# ultra-low-noise-psu-NEG-v0001.net
KiCad netlist of a schematic drawn in EAGLE
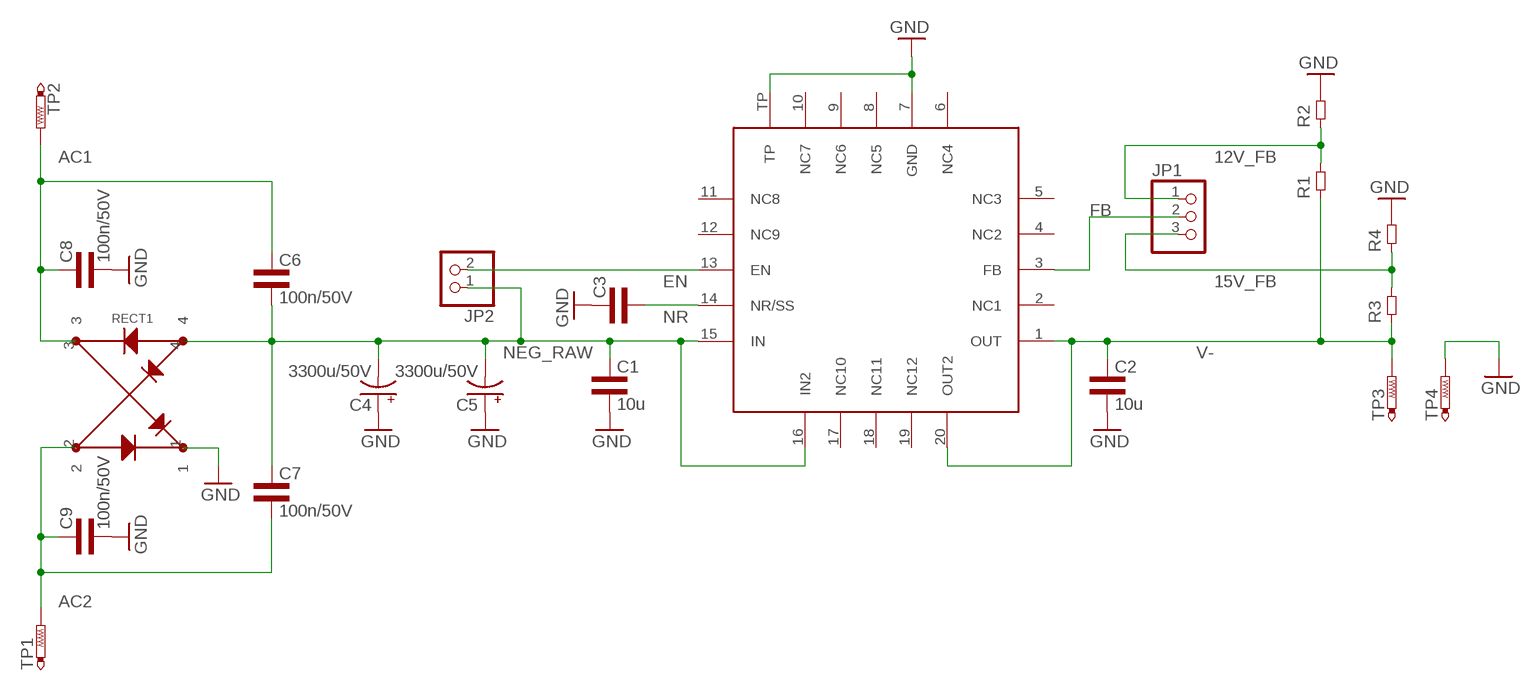
[diagram p0: schematic, sheet 1]

(export (version "E")
  (design (tool "Eeschema 10.0.6"))
  (components
    (comp (ref "C1")
      (value "10u")
      (footprint "eagle-import:0805L3")
      (libsource (lib "eagle-import") (part "CAP0805L3"))
    )
    (comp (ref "C2")
      (value "10u")
      (footprint "eagle-import:0805L3")
      (libsource (lib "eagle-import") (part "CAP0805L3"))
    )
    (comp (ref "C3")
      (value "CAP0603L3")
      (footprint "eagle-import:0603L3")
      (libsource (lib "eagle-import") (part "CAP0603L3"))
    )
    (comp (ref "C4")
      (value "3300u/50V")
      (footprint "eagle-import:E7,5-18")
      (libsource (lib "eagle-import") (part "CPOL-USE7.5-18"))
    )
    (comp (ref "C5")
      (value "3300u/50V")
      (footprint "eagle-import:E7,5-18")
      (libsource (lib "eagle-import") (part "CPOL-USE7.5-18"))
    )
    (comp (ref "C6")
      (value "100n/50V")
      (footprint "eagle-import:0805L3")
      (libsource (lib "eagle-import") (part "CAP0805L3"))
    )
    (comp (ref "C7")
      (value "100n/50V")
      (footprint "eagle-import:0805L3")
      (libsource (lib "eagle-import") (part "CAP0805L3"))
    )
    (comp (ref "C8")
      (value "100n/50V")
      (footprint "eagle-import:0805L3")
      (libsource (lib "eagle-import") (part "CAP0805L3"))
    )
    (comp (ref "C9")
      (value "100n/50V")
      (footprint "eagle-import:0805L3")
      (libsource (lib "eagle-import") (part "CAP0805L3"))
    )
    (comp (ref "JP1")
      (value "PINHD-1X3")
      (footprint "eagle-import:1X03")
      (libsource (lib "eagle-import") (part "PINHD-1X3"))
    )
    (comp (ref "JP2")
      (value "PINHD-1X2")
      (footprint "eagle-import:1X02")
      (libsource (lib "eagle-import") (part "PINHD-1X2"))
    )
    (comp (ref "R1")
      (value "RES0603L3")
      (footprint "eagle-import:0603L3")
      (libsource (lib "eagle-import") (part "RES0603L3"))
    )
    (comp (ref "R2")
      (value "RES0603L3")
      (footprint "eagle-import:0603L3")
      (libsource (lib "eagle-import") (part "RES0603L3"))
    )
    (comp (ref "R3")
      (value "RES0603L3")
      (footprint "eagle-import:0603L3")
      (libsource (lib "eagle-import") (part "RES0603L3"))
    )
    (comp (ref "R4")
      (value "RES0603L3")
      (footprint "eagle-import:0603L3")
      (libsource (lib "eagle-import") (part "RES0603L3"))
    )
    (comp (ref "RECT1")
      (value "RECTIFIER_Z4GP206")
      (footprint "eagle-import:RECTIFIER_ABS-4")
      (libsource (lib "eagle-import") (part "RECTIFIER_Z4GP206"))
    )
    (comp (ref "TP1")
      (value "PTR1PAD1-20")
      (footprint "eagle-import:P1-20")
      (libsource (lib "eagle-import") (part "PTR1PAD1-20"))
    )
    (comp (ref "TP2")
      (value "PTR1PAD1-20")
      (footprint "eagle-import:P1-20")
      (libsource (lib "eagle-import") (part "PTR1PAD1-20"))
    )
    (comp (ref "TP3")
      (value "PTR1PAD1-20")
      (footprint "eagle-import:P1-20")
      (libsource (lib "eagle-import") (part "PTR1PAD1-20"))
    )
    (comp (ref "TP4")
      (value "PTR1PAD1-20")
      (footprint "eagle-import:P1-20")
      (libsource (lib "eagle-import") (part "PTR1PAD1-20"))
    )
    (comp (ref "U$1")
      (value "POWER-SUPPLY_POS_V1_TI_LDO_TPS7A3301RGWT")
      (footprint "eagle-import:POWER-SUPPLY_POS_V1_TI_LDO_VQFN-20")
      (libsource (lib "eagle-import") (part "POWER-SUPPLY_POS_V1_TI_LDO_TPS7A3301RGWT"))
    )
  )
  (nets
    (net (code "1") (name "/12V_FB") (class "Default")
      (node (ref "JP1") (pin "1") (pinfunction "1_1") (pintype "passive"))
      (node (ref "R1") (pin "P$2") (pinfunction "2_P$2") (pintype "bidirectional"))
      (node (ref "R2") (pin "P$1") (pinfunction "1_P$1") (pintype "bidirectional"))
    )
    (net (code "2") (name "/15V_FB") (class "Default")
      (node (ref "JP1") (pin "3") (pinfunction "3_3") (pintype "passive"))
      (node (ref "R3") (pin "P$2") (pinfunction "2_P$2") (pintype "bidirectional"))
      (node (ref "R4") (pin "P$1") (pinfunction "1_P$1") (pintype "bidirectional"))
    )
    (net (code "3") (name "/AC1") (class "Default")
      (node (ref "C6") (pin "1") (pinfunction "1_1") (pintype "bidirectional"))
      (node (ref "C8") (pin "1") (pinfunction "1_1") (pintype "bidirectional"))
      (node (ref "RECT1") (pin "3") (pinfunction "3_3") (pintype "bidirectional"))
      (node (ref "TP2") (pin "TP") (pinfunction "TP_TP") (pintype "input"))
    )
    (net (code "4") (name "/AC2") (class "Default")
      (node (ref "C7") (pin "2") (pinfunction "2_2") (pintype "bidirectional"))
      (node (ref "C9") (pin "1") (pinfunction "1_1") (pintype "bidirectional"))
      (node (ref "RECT1") (pin "2") (pinfunction "2_2") (pintype "bidirectional"))
      (node (ref "TP1") (pin "TP") (pinfunction "TP_TP") (pintype "input"))
    )
    (net (code "5") (name "/EN") (class "Default")
      (node (ref "JP2") (pin "2") (pinfunction "2_2") (pintype "passive"))
      (node (ref "U$1") (pin "13") (pinfunction "EN_13") (pintype "bidirectional"))
    )
    (net (code "6") (name "/FB") (class "Default")
      (node (ref "JP1") (pin "2") (pinfunction "2_2") (pintype "passive"))
      (node (ref "U$1") (pin "3") (pinfunction "FB_3") (pintype "bidirectional"))
    )
    (net (code "7") (name "/NEG_RAW") (class "Default")
      (node (ref "C1") (pin "1") (pinfunction "1_1") (pintype "bidirectional"))
      (node (ref "C4") (pin "-") (pinfunction "-_-") (pintype "passive"))
      (node (ref "C5") (pin "-") (pinfunction "-_-") (pintype "passive"))
      (node (ref "C6") (pin "2") (pinfunction "2_2") (pintype "bidirectional"))
      (node (ref "C7") (pin "1") (pinfunction "1_1") (pintype "bidirectional"))
      (node (ref "JP2") (pin "1") (pinfunction "1_1") (pintype "passive"))
      (node (ref "RECT1") (pin "4") (pinfunction "4_4") (pintype "bidirectional"))
      (node (ref "U$1") (pin "15") (pinfunction "IN_15") (pintype "bidirectional"))
      (node (ref "U$1") (pin "16") (pinfunction "IN2_16") (pintype "bidirectional"))
    )
    (net (code "8") (name "/NR") (class "Default")
      (node (ref "C3") (pin "P$2") (pinfunction "2_P$2") (pintype "bidirectional"))
      (node (ref "U$1") (pin "14") (pinfunction "NR/SS_14") (pintype "bidirectional"))
    )
    (net (code "9") (name "/V-") (class "Default")
      (node (ref "C2") (pin "1") (pinfunction "1_1") (pintype "bidirectional"))
      (node (ref "R1") (pin "P$1") (pinfunction "1_P$1") (pintype "bidirectional"))
      (node (ref "R3") (pin "P$1") (pinfunction "1_P$1") (pintype "bidirectional"))
      (node (ref "TP3") (pin "TP") (pinfunction "TP_TP") (pintype "input"))
      (node (ref "U$1") (pin "1") (pinfunction "OUT_1") (pintype "bidirectional"))
      (node (ref "U$1") (pin "20") (pinfunction "OUT2_20") (pintype "bidirectional"))
    )
    (net (code "10") (name "GND") (class "Default")
      (node (ref "C1") (pin "2") (pinfunction "2_2") (pintype "bidirectional"))
      (node (ref "C2") (pin "2") (pinfunction "2_2") (pintype "bidirectional"))
      (node (ref "C3") (pin "P$1") (pinfunction "1_P$1") (pintype "bidirectional"))
      (node (ref "C4") (pin "+") (pinfunction "+_+") (pintype "passive"))
      (node (ref "C5") (pin "+") (pinfunction "+_+") (pintype "passive"))
      (node (ref "C8") (pin "2") (pinfunction "2_2") (pintype "bidirectional"))
      (node (ref "C9") (pin "2") (pinfunction "2_2") (pintype "bidirectional"))
      (node (ref "R2") (pin "P$2") (pinfunction "2_P$2") (pintype "bidirectional"))
      (node (ref "R4") (pin "P$2") (pinfunction "2_P$2") (pintype "bidirectional"))
      (node (ref "RECT1") (pin "1") (pinfunction "1_1") (pintype "bidirectional"))
      (node (ref "TP4") (pin "TP") (pinfunction "TP_TP") (pintype "input"))
      (node (ref "U$1") (pin "7") (pinfunction "GND_7") (pintype "bidirectional"))
      (node (ref "U$1") (pin "TP") (pinfunction "TP_TP") (pintype "bidirectional"))
    )
    (net (code "11") (name "unconnected-(U$1-NC1-Pad2)") (class "Default")
      (node (ref "U$1") (pin "2") (pinfunction "NC1_2") (pintype "bidirectional"))
    )
    (net (code "12") (name "unconnected-(U$1-NC2-Pad4)") (class "Default")
      (node (ref "U$1") (pin "4") (pinfunction "NC2_4") (pintype "bidirectional"))
    )
    (net (code "13") (name "unconnected-(U$1-NC3-Pad5)") (class "Default")
      (node (ref "U$1") (pin "5") (pinfunction "NC3_5") (pintype "bidirectional"))
    )
    (net (code "14") (name "unconnected-(U$1-NC4-Pad6)") (class "Default")
      (node (ref "U$1") (pin "6") (pinfunction "NC4_6") (pintype "bidirectional"))
    )
    (net (code "15") (name "unconnected-(U$1-NC5-Pad8)") (class "Default")
      (node (ref "U$1") (pin "8") (pinfunction "NC5_8") (pintype "bidirectional"))
    )
    (net (code "16") (name "unconnected-(U$1-NC6-Pad9)") (class "Default")
      (node (ref "U$1") (pin "9") (pinfunction "NC6_9") (pintype "bidirectional"))
    )
    (net (code "17") (name "unconnected-(U$1-NC7-Pad10)") (class "Default")
      (node (ref "U$1") (pin "10") (pinfunction "NC7_10") (pintype "bidirectional"))
    )
    (net (code "18") (name "unconnected-(U$1-NC8-Pad11)") (class "Default")
      (node (ref "U$1") (pin "11") (pinfunction "NC8_11") (pintype "bidirectional"))
    )
    (net (code "19") (name "unconnected-(U$1-NC9-Pad12)") (class "Default")
      (node (ref "U$1") (pin "12") (pinfunction "NC9_12") (pintype "bidirectional"))
    )
    (net (code "20") (name "unconnected-(U$1-NC10-Pad17)") (class "Default")
      (node (ref "U$1") (pin "17") (pinfunction "NC10_17") (pintype "bidirectional"))
    )
    (net (code "21") (name "unconnected-(U$1-NC11-Pad18)") (class "Default")
      (node (ref "U$1") (pin "18") (pinfunction "NC11_18") (pintype "bidirectional"))
    )
    (net (code "22") (name "unconnected-(U$1-NC12-Pad19)") (class "Default")
      (node (ref "U$1") (pin "19") (pinfunction "NC12_19") (pintype "bidirectional"))
    )
  )
)
